# RTC_V2_pb.net
KiCad netlist of a schematic drawn in EAGLE
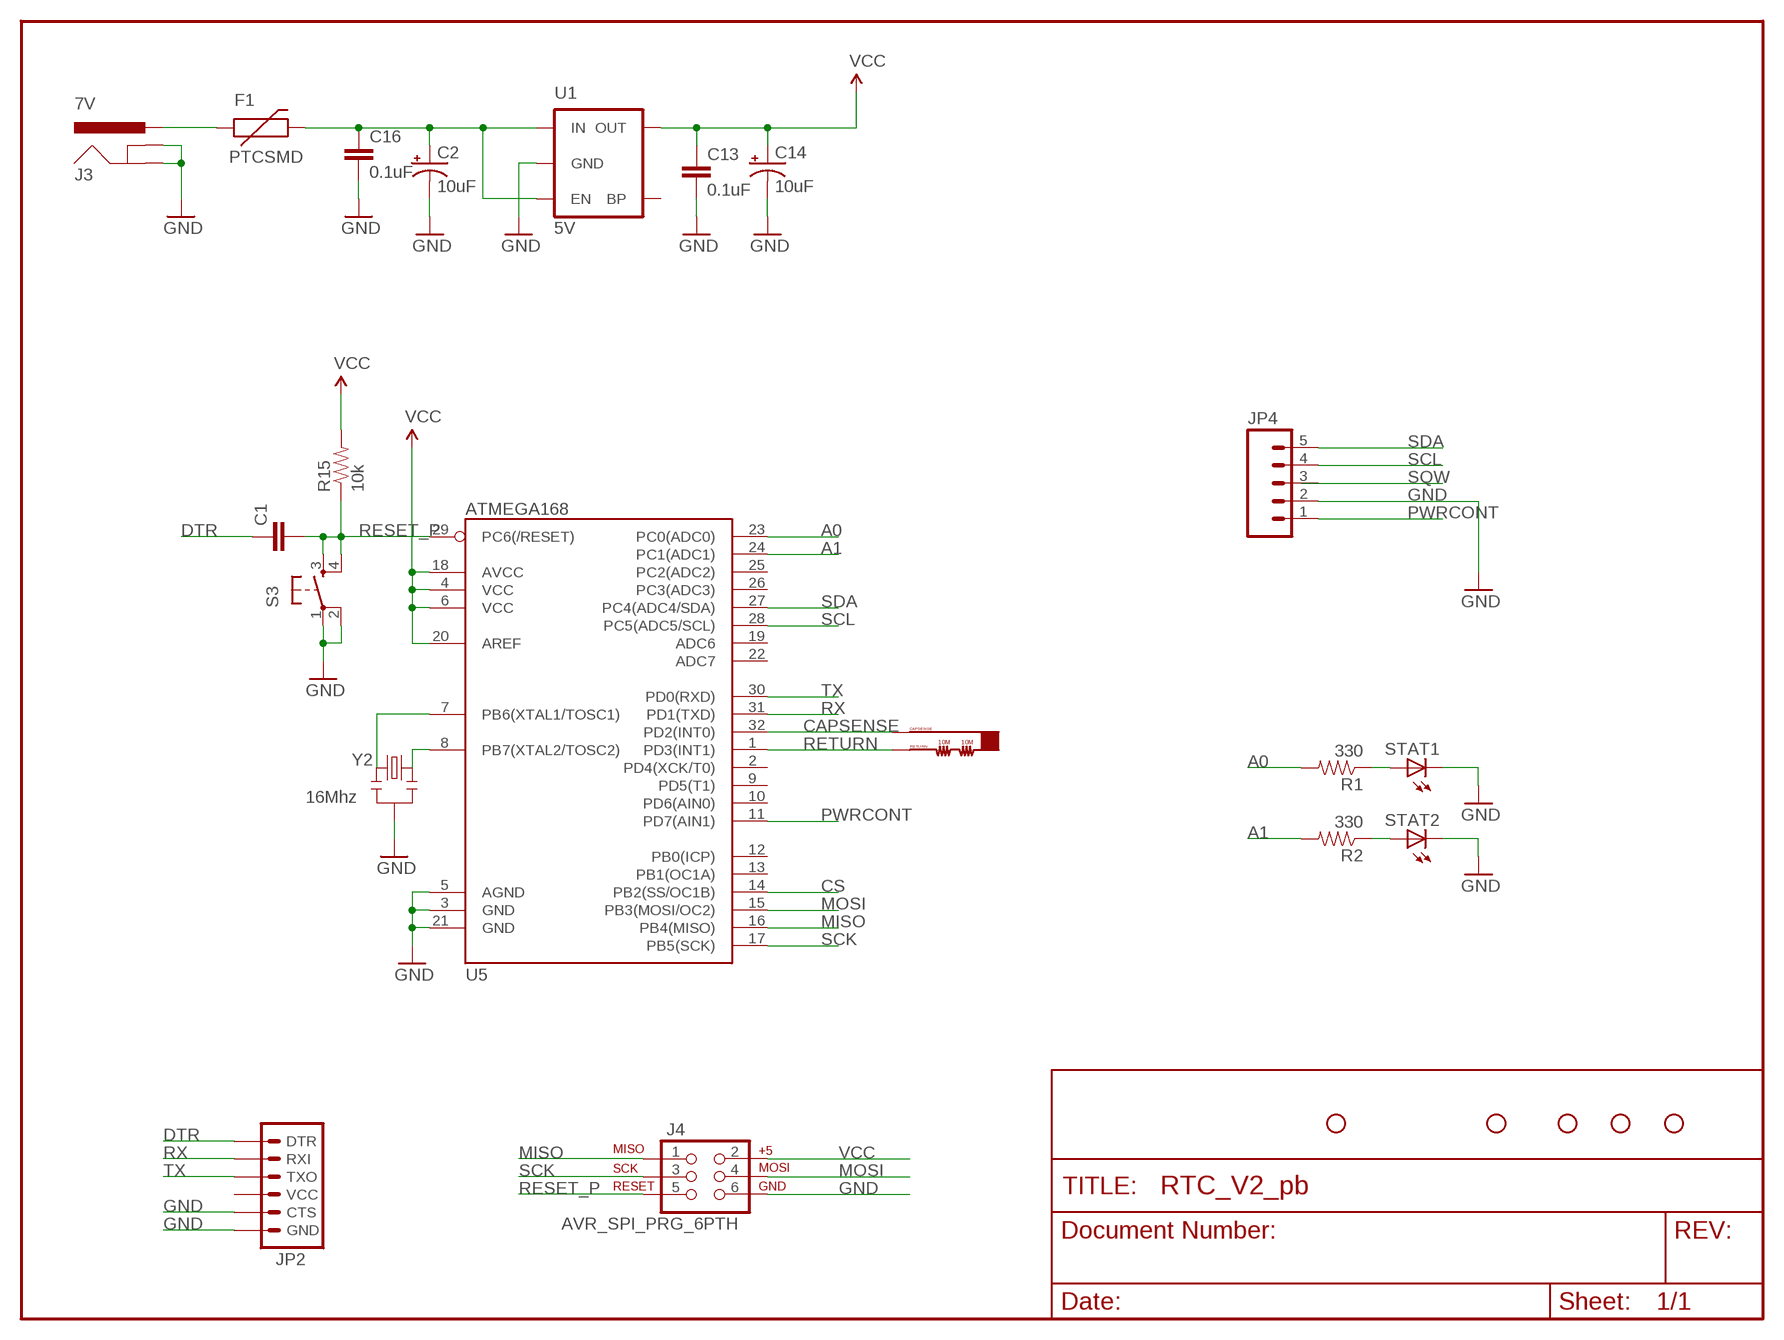
[diagram p0: schematic, sheet 1]

(export (version "E")
  (design (tool "Eeschema 10.0.6"))
  (components
    (comp (ref "C1")
      (value "CAP0603-CAP")
      (footprint "eagle-import:0603-CAP")
      (libsource (lib "eagle-import") (part "CAP0603-CAP"))
    )
    (comp (ref "C2")
      (value "10uF")
      (footprint "eagle-import:EIA3216")
      (libsource (lib "eagle-import") (part "CAP_POL1206"))
    )
    (comp (ref "C13")
      (value "0.1uF")
      (footprint "eagle-import:0603-CAP")
      (libsource (lib "eagle-import") (part "CAP0603-CAP"))
    )
    (comp (ref "C14")
      (value "10uF")
      (footprint "eagle-import:EIA3216")
      (libsource (lib "eagle-import") (part "CAP_POL1206"))
    )
    (comp (ref "C16")
      (value "0.1uF")
      (footprint "eagle-import:0603-CAP")
      (libsource (lib "eagle-import") (part "CAP0603-CAP"))
    )
    (comp (ref "F1")
      (value "PTCSMD")
      (footprint "eagle-import:PTC-1206")
      (libsource (lib "eagle-import") (part "PTCSMD"))
    )
    (comp (ref "J3")
      (value "7V")
      (footprint "eagle-import:POWER_JACK_PTH_LOCK")
      (libsource (lib "eagle-import") (part "POWER_JACKPTH_LOCK"))
    )
    (comp (ref "J4")
      (value "AVR_SPI_PRG_6PTH")
      (footprint "eagle-import:2X3")
      (libsource (lib "eagle-import") (part "AVR_SPI_PRG_6PTH"))
    )
    (comp (ref "JP1")
      (value "STAND-OFFTIGHT")
      (footprint "eagle-import:STAND-OFF-TIGHT")
      (libsource (lib "eagle-import") (part "STAND-OFFTIGHT"))
    )
    (comp (ref "JP2")
      (value "ARDUINO_SERIAL_PROGRAMPTH")
      (footprint "eagle-import:1X06")
      (libsource (lib "eagle-import") (part "ARDUINO_SERIAL_PROGRAMPTH"))
    )
    (comp (ref "JP4")
      (value "M05PTH_LONGPADS")
      (footprint "eagle-import:1X05_LONGPADS")
      (libsource (lib "eagle-import") (part "M05PTH_LONGPADS"))
    )
    (comp (ref "JP7")
      (value "STAND-OFFTIGHT")
      (footprint "eagle-import:STAND-OFF-TIGHT")
      (libsource (lib "eagle-import") (part "STAND-OFFTIGHT"))
    )
    (comp (ref "JP8")
      (value "STAND-OFFTIGHT")
      (footprint "eagle-import:STAND-OFF-TIGHT")
      (libsource (lib "eagle-import") (part "STAND-OFFTIGHT"))
    )
    (comp (ref "JP9")
      (value "STAND-OFFTIGHT")
      (footprint "eagle-import:STAND-OFF-TIGHT")
      (libsource (lib "eagle-import") (part "STAND-OFFTIGHT"))
    )
    (comp (ref "JP10")
      (value "STAND-OFFTIGHT")
      (footprint "eagle-import:STAND-OFF-TIGHT")
      (libsource (lib "eagle-import") (part "STAND-OFFTIGHT"))
    )
    (comp (ref "R1")
      (value "330")
      (footprint "eagle-import:0603-RES")
      (libsource (lib "eagle-import") (part "RESISTOR0603-RES"))
    )
    (comp (ref "R2")
      (value "330")
      (footprint "eagle-import:0603-RES")
      (libsource (lib "eagle-import") (part "RESISTOR0603-RES"))
    )
    (comp (ref "R15")
      (value "10k")
      (footprint "eagle-import:0603-RES")
      (libsource (lib "eagle-import") (part "RESISTOR0603-RES"))
    )
    (comp (ref "S3")
      (value "TAC_SWITCHPTH")
      (footprint "eagle-import:TACTILE-PTH")
      (libsource (lib "eagle-import") (part "TAC_SWITCHPTH"))
    )
    (comp (ref "STAT1")
      (value "Yellow")
      (footprint "eagle-import:LED-1206")
      (libsource (lib "eagle-import") (part "LED1206"))
    )
    (comp (ref "STAT2")
      (value "Yellow")
      (footprint "eagle-import:LED-1206")
      (libsource (lib "eagle-import") (part "LED1206"))
    )
    (comp (ref "U$3")
      (value "CAPSENSE_BUTTON")
      (footprint "eagle-import:CAPSENSE_BUTTON")
      (libsource (lib "eagle-import") (part "CAPSENSE_BUTTON"))
    )
    (comp (ref "U1")
      (value "3.3V")
      (footprint "eagle-import:SOT23-5")
      (libsource (lib "eagle-import") (part "V_REG_LDOSMD"))
    )
    (comp (ref "U5")
      (value "ATMEGA168")
      (footprint "eagle-import:TQFP32-08")
      (libsource (lib "eagle-import") (part "ATMEGA168"))
    )
    (comp (ref "Y2")
      (value "8MHz")
      (footprint "eagle-import:RESONATOR-SMD")
      (libsource (lib "eagle-import") (part "RESONATORSMD"))
    )
  )
  (nets
    (net (code "1") (name "/A0") (class "Default")
      (node (ref "R1") (pin "2") (pinfunction "2_2") (pintype "passive"))
      (node (ref "U5") (pin "23") (pinfunction "PC0(ADC0)_23") (pintype "bidirectional"))
    )
    (net (code "2") (name "/A1") (class "Default")
      (node (ref "R2") (pin "2") (pinfunction "2_2") (pintype "passive"))
      (node (ref "U5") (pin "24") (pinfunction "PC1(ADC1)_24") (pintype "bidirectional"))
    )
    (net (code "3") (name "/CAPSENSE") (class "Default")
      (node (ref "U$3") (pin "CAPSENSE") (pinfunction "CAPSENSE_CAPSENSE") (pintype "bidirectional"))
      (node (ref "U5") (pin "32") (pinfunction "PD2(INT0)_32") (pintype "bidirectional"))
    )
    (net (code "4") (name "/CS") (class "Default")
      (node (ref "U5") (pin "14") (pinfunction "PB2(SS/OC1B)_14") (pintype "bidirectional"))
    )
    (net (code "5") (name "/DTR") (class "Default")
      (node (ref "C1") (pin "1") (pinfunction "1_1") (pintype "passive"))
      (node (ref "JP2") (pin "1") (pinfunction "DTR_1") (pintype "passive"))
    )
    (net (code "6") (name "/MISO") (class "Default")
      (node (ref "J4") (pin "1") (pinfunction "1_1") (pintype "passive"))
      (node (ref "U5") (pin "16") (pinfunction "PB4(MISO)_16") (pintype "bidirectional"))
    )
    (net (code "7") (name "/MOSI") (class "Default")
      (node (ref "J4") (pin "4") (pinfunction "4_4") (pintype "passive"))
      (node (ref "U5") (pin "15") (pinfunction "PB3(MOSI/OC2)_15") (pintype "bidirectional"))
    )
    (net (code "8") (name "/PWRCONT") (class "Default")
      (node (ref "JP4") (pin "1") (pinfunction "1_1") (pintype "passive"))
      (node (ref "U5") (pin "11") (pinfunction "PD7(AIN1)_11") (pintype "bidirectional"))
    )
    (net (code "9") (name "/RESET_P") (class "Default")
      (node (ref "C1") (pin "2") (pinfunction "2_2") (pintype "passive"))
      (node (ref "J4") (pin "5") (pinfunction "5_5") (pintype "passive"))
      (node (ref "R15") (pin "1") (pinfunction "1_1") (pintype "passive"))
      (node (ref "S3") (pin "3") (pinfunction "3_3") (pintype "passive"))
      (node (ref "S3") (pin "4") (pinfunction "4_4") (pintype "passive"))
      (node (ref "U5") (pin "29") (pinfunction "PC6(/RESET)_29") (pintype "bidirectional"))
    )
    (net (code "10") (name "/RETURN") (class "Default")
      (node (ref "U$3") (pin "RETURN") (pinfunction "RETURN_RETURN") (pintype "bidirectional"))
      (node (ref "U5") (pin "1") (pinfunction "PD3(INT1)_1") (pintype "bidirectional"))
    )
    (net (code "11") (name "/RX") (class "Default")
      (node (ref "JP2") (pin "2") (pinfunction "RXI_2") (pintype "passive"))
      (node (ref "U5") (pin "31") (pinfunction "PD1(TXD)_31") (pintype "bidirectional"))
    )
    (net (code "12") (name "/SCK") (class "Default")
      (node (ref "J4") (pin "3") (pinfunction "3_3") (pintype "passive"))
      (node (ref "U5") (pin "17") (pinfunction "PB5(SCK)_17") (pintype "bidirectional"))
    )
    (net (code "13") (name "/SCL") (class "Default")
      (node (ref "JP4") (pin "4") (pinfunction "4_4") (pintype "passive"))
      (node (ref "U5") (pin "28") (pinfunction "PC5(ADC5/SCL)_28") (pintype "bidirectional"))
    )
    (net (code "14") (name "/SDA") (class "Default")
      (node (ref "JP4") (pin "5") (pinfunction "5_5") (pintype "passive"))
      (node (ref "U5") (pin "27") (pinfunction "PC4(ADC4/SDA)_27") (pintype "bidirectional"))
    )
    (net (code "16") (name "/TX") (class "Default")
      (node (ref "JP2") (pin "3") (pinfunction "TXO_3") (pintype "passive"))
      (node (ref "U5") (pin "30") (pinfunction "PD0(RXD)_30") (pintype "bidirectional"))
    )
    (net (code "17") (name "GND") (class "Default")
      (node (ref "C13") (pin "2") (pinfunction "2_2") (pintype "passive"))
      (node (ref "C14") (pin "C") (pinfunction "-_C") (pintype "passive"))
      (node (ref "C16") (pin "2") (pinfunction "2_2") (pintype "passive"))
      (node (ref "C2") (pin "C") (pinfunction "-_C") (pintype "passive"))
      (node (ref "J3") (pin "GND") (pinfunction "GND_GND") (pintype "bidirectional"))
      (node (ref "J3") (pin "GNDBREAK") (pinfunction "GNDBREAK_GNDBREAK") (pintype "bidirectional"))
      (node (ref "J4") (pin "6") (pinfunction "6_6") (pintype "passive"))
      (node (ref "JP2") (pin "5") (pinfunction "CTS_5") (pintype "passive"))
      (node (ref "JP2") (pin "6") (pinfunction "GND_6") (pintype "passive"))
      (node (ref "JP4") (pin "2") (pinfunction "2_2") (pintype "passive"))
      (node (ref "S3") (pin "1") (pinfunction "1_1") (pintype "passive"))
      (node (ref "S3") (pin "2") (pinfunction "2_2") (pintype "passive"))
      (node (ref "STAT1") (pin "C") (pinfunction "C_C") (pintype "passive"))
      (node (ref "STAT2") (pin "C") (pinfunction "C_C") (pintype "passive"))
      (node (ref "U1") (pin "2") (pinfunction "GND_2") (pintype "input"))
      (node (ref "U5") (pin "21") (pinfunction "GND_21") (pintype "bidirectional"))
      (node (ref "U5") (pin "3") (pinfunction "GND_3") (pintype "bidirectional"))
      (node (ref "U5") (pin "5") (pinfunction "AGND_5") (pintype "bidirectional"))
      (node (ref "Y2") (pin "2") (pinfunction "2_2") (pintype "passive"))
    )
    (net (code "18") (name "Net-(C2-+)") (class "Default")
      (node (ref "C16") (pin "1") (pinfunction "1_1") (pintype "passive"))
      (node (ref "C2") (pin "A") (pinfunction "+_A") (pintype "passive"))
      (node (ref "F1") (pin "2") (pinfunction "2_2") (pintype "bidirectional"))
      (node (ref "U1") (pin "1") (pinfunction "IN_1") (pintype "input"))
      (node (ref "U1") (pin "3") (pinfunction "EN_3") (pintype "input"))
    )
    (net (code "19") (name "Net-(F1-Pad1)") (class "Default")
      (node (ref "F1") (pin "1") (pinfunction "1_1") (pintype "bidirectional"))
      (node (ref "J3") (pin "PWR") (pinfunction "PWR_PWR") (pintype "bidirectional"))
    )
    (net (code "20") (name "Net-(R1-Pad1)") (class "Default")
      (node (ref "R1") (pin "1") (pinfunction "1_1") (pintype "passive"))
      (node (ref "STAT1") (pin "A") (pinfunction "A_A") (pintype "passive"))
    )
    (net (code "21") (name "Net-(R2-Pad1)") (class "Default")
      (node (ref "R2") (pin "1") (pinfunction "1_1") (pintype "passive"))
      (node (ref "STAT2") (pin "A") (pinfunction "A_A") (pintype "passive"))
    )
    (net (code "22") (name "Net-(U5-PB6(XTAL1{slash}TOSC1))") (class "Default")
      (node (ref "U5") (pin "7") (pinfunction "PB6(XTAL1/TOSC1)_7") (pintype "bidirectional"))
      (node (ref "Y2") (pin "1") (pinfunction "1_1") (pintype "passive"))
    )
    (net (code "23") (name "Net-(U5-PB7(XTAL2{slash}TOSC2))") (class "Default")
      (node (ref "U5") (pin "8") (pinfunction "PB7(XTAL2/TOSC2)_8") (pintype "bidirectional"))
      (node (ref "Y2") (pin "3") (pinfunction "3_3") (pintype "passive"))
    )
    (net (code "24") (name "VCC") (class "Default")
      (node (ref "C13") (pin "1") (pinfunction "1_1") (pintype "passive"))
      (node (ref "C14") (pin "A") (pinfunction "+_A") (pintype "passive"))
      (node (ref "J4") (pin "2") (pinfunction "2_2") (pintype "passive"))
      (node (ref "R15") (pin "2") (pinfunction "2_2") (pintype "passive"))
      (node (ref "U1") (pin "5") (pinfunction "OUT_5") (pintype "passive"))
      (node (ref "U5") (pin "18") (pinfunction "AVCC_18") (pintype "bidirectional"))
      (node (ref "U5") (pin "20") (pinfunction "AREF_20") (pintype "bidirectional"))
      (node (ref "U5") (pin "4") (pinfunction "VCC_4") (pintype "bidirectional"))
      (node (ref "U5") (pin "6") (pinfunction "VCC_6") (pintype "bidirectional"))
    )
    (net (code "25") (name "unconnected-(JP2-VCC-Pad4)") (class "Default")
      (node (ref "JP2") (pin "4") (pinfunction "VCC_4") (pintype "passive"))
    )
    (net (code "26") (name "unconnected-(JP4-Pad3)") (class "Default")
      (node (ref "JP4") (pin "3") (pinfunction "3_3") (pintype "passive"))
    )
    (net (code "27") (name "unconnected-(U1-BP-Pad4)") (class "Default")
      (node (ref "U1") (pin "4") (pinfunction "BP_4") (pintype "input"))
    )
    (net (code "28") (name "unconnected-(U5-ADC6-Pad19)") (class "Default")
      (node (ref "U5") (pin "19") (pinfunction "ADC6_19") (pintype "bidirectional"))
    )
    (net (code "29") (name "unconnected-(U5-ADC7-Pad22)") (class "Default")
      (node (ref "U5") (pin "22") (pinfunction "ADC7_22") (pintype "bidirectional"))
    )
    (net (code "30") (name "unconnected-(U5-PB0(ICP)-Pad12)") (class "Default")
      (node (ref "U5") (pin "12") (pinfunction "PB0(ICP)_12") (pintype "bidirectional"))
    )
    (net (code "31") (name "unconnected-(U5-PB1(OC1A)-Pad13)") (class "Default")
      (node (ref "U5") (pin "13") (pinfunction "PB1(OC1A)_13") (pintype "bidirectional"))
    )
    (net (code "32") (name "unconnected-(U5-PC2(ADC2)-Pad25)") (class "Default")
      (node (ref "U5") (pin "25") (pinfunction "PC2(ADC2)_25") (pintype "bidirectional"))
    )
    (net (code "33") (name "unconnected-(U5-PC3(ADC3)-Pad26)") (class "Default")
      (node (ref "U5") (pin "26") (pinfunction "PC3(ADC3)_26") (pintype "bidirectional"))
    )
    (net (code "34") (name "unconnected-(U5-PD4(XCK{slash}T0)-Pad2)") (class "Default")
      (node (ref "U5") (pin "2") (pinfunction "PD4(XCK/T0)_2") (pintype "bidirectional"))
    )
    (net (code "35") (name "unconnected-(U5-PD5(T1)-Pad9)") (class "Default")
      (node (ref "U5") (pin "9") (pinfunction "PD5(T1)_9") (pintype "bidirectional"))
    )
    (net (code "36") (name "unconnected-(U5-PD6(AIN0)-Pad10)") (class "Default")
      (node (ref "U5") (pin "10") (pinfunction "PD6(AIN0)_10") (pintype "bidirectional"))
    )
  )
)
